# TP1_NodoWiFi_Pwr_Rev0.net
KiCad netlist of a schematic drawn in Altium Designer
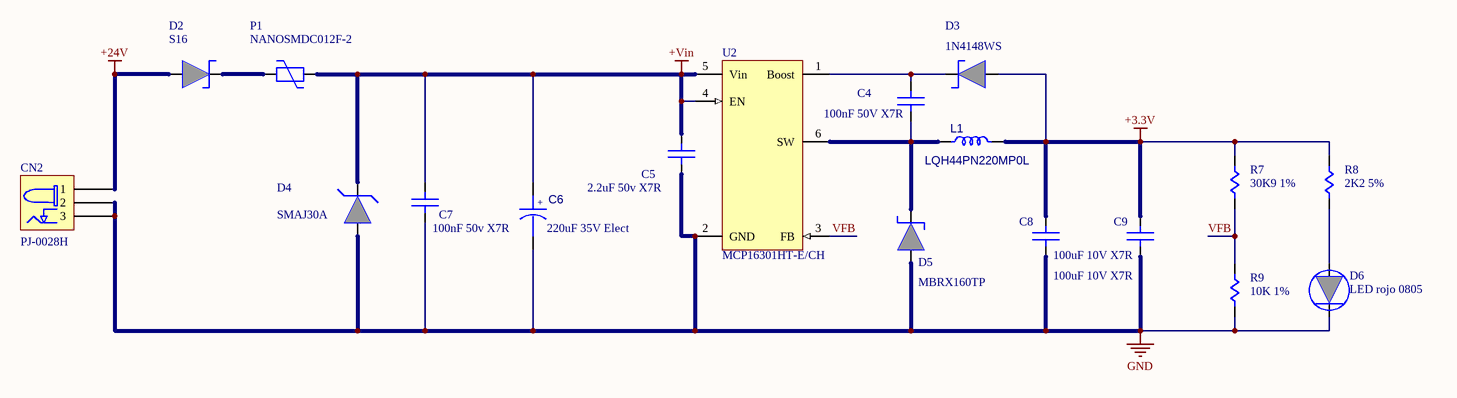
[diagram p0: TP1_NodoWiFi_Pwr_Rev0.SchDoc]

(export (version "E")
  (design (tool "Eeschema 10.0.6"))
  (components
    (comp (ref "C4")
      (value "100nF 50V X7R")
      (footprint "IDCI_WifiNode:C_0805")
      (description "capacitor no polarizado")
      (libsource (lib "WifiNode") (part "Capacitor_NoP"))
    )
    (comp (ref "C5")
      (value "2.2uF 50v X7R")
      (footprint "IDCI_WifiNode:C_0805")
      (description "capacitor no polarizado")
      (libsource (lib "WifiNode") (part "Capacitor_NoP"))
    )
    (comp (ref "C6")
      (value "220uF 35V Elect")
      (footprint "IDCI_WifiNode:C_RAD_0.135_H_8X12_S")
      (description "Polarized Capacitor")
      (libsource (lib "WifiNode") (part "CAP_P"))
    )
    (comp (ref "C7")
      (value "100nF 50v X7R")
      (footprint "IDCI_WifiNode:C_0805")
      (description "capacitor no polarizado")
      (libsource (lib "WifiNode") (part "Capacitor_NoP"))
    )
    (comp (ref "C8")
      (value "100uF 10V X7R")
      (footprint "IDCI_WifiNode:C_0805")
      (description "capacitor no polarizado")
      (libsource (lib "WifiNode") (part "Capacitor_NoP"))
    )
    (comp (ref "C9")
      (value "100uF 10V X7R")
      (footprint "IDCI_WifiNode:C_0805")
      (description "capacitor no polarizado")
      (libsource (lib "WifiNode") (part "Capacitor_NoP"))
    )
    (comp (ref "CN2")
      (value "PJ-0028H")
      (footprint "IDCI_WifiNode:PJ002B")
      (description "Conector PJ")
      (libsource (lib "WifiNode") (part "PJ-0028H"))
    )
    (comp (ref "D2")
      (value "S16")
      (footprint "IDCI_WifiNode:D_0805")
      (description "Schottky")
      (libsource (lib "WifiNode") (part "Diodo Schottky"))
    )
    (comp (ref "D3")
      (value "1N4148WS")
      (footprint "IDCI_WifiNode:D_0805")
      (description "Schottky")
      (libsource (lib "WifiNode") (part "Diodo Schottky"))
    )
    (comp (ref "D4")
      (value "SMAJ30A")
      (footprint "IDCI_WifiNode:D_SMA")
      (description "Zener")
      (libsource (lib "WifiNode") (part "Diodo Zener"))
    )
    (comp (ref "D5")
      (value "MBRX160TP")
      (footprint "IDCI_WifiNode:SOD_123")
      (description "Schottky")
      (libsource (lib "WifiNode") (part "Diodo Schottky"))
    )
    (comp (ref "D6")
      (value "LED rojo 0805")
      (footprint "IDCI_WifiNode:D_0805")
      (description "LED")
      (libsource (lib "WifiNode") (part "Diodo LED"))
    )
    (comp (ref "L1")
      (value "LQH44PN220MP0L")
      (footprint "IDCI_WifiNode:LQH44")
      (description "Inductor")
      (libsource (lib "WifiNode") (part "IND"))
    )
    (comp (ref "P1")
      (value "NANOSMDC012F-2")
      (footprint "IDCI_WifiNode:C_1206")
      (description "Poly Switch")
      (libsource (lib "WifiNode") (part "Poly Switch"))
    )
    (comp (ref "R7")
      (value "30K9 1%")
      (footprint "IDCI_WifiNode:R_0805")
      (description "Resistor")
      (libsource (lib "WifiNode") (part "Resistencia"))
    )
    (comp (ref "R8")
      (value "2K2 5%")
      (footprint "IDCI_WifiNode:R_0805")
      (description "Resistor")
      (libsource (lib "WifiNode") (part "Resistencia"))
    )
    (comp (ref "R9")
      (value "10K 1%")
      (footprint "IDCI_WifiNode:R_0805")
      (description "Resistor")
      (libsource (lib "WifiNode") (part "Resistencia"))
    )
    (comp (ref "U2")
      (value "MCP16301HT-E/CH")
      (footprint "IDCI_WifiNode:SOT23-6")
      (description "IC_DC/DC Buck controler")
      (libsource (lib "WifiNode") (part "MCP16301"))
    )
  )
  (nets
    (net (code "1") (name "+3.3V") (class "Default")
      (node (ref "C8") (pin "2") (pinfunction "Cap_2") (pintype "passive"))
      (node (ref "C9") (pin "2") (pinfunction "Cap_2") (pintype "passive"))
      (node (ref "D3") (pin "1") (pinfunction "Cap_1") (pintype "passive"))
      (node (ref "L1") (pin "2") (pinfunction "2_2") (pintype "passive"))
      (node (ref "R7") (pin "2") (pinfunction "Cap_2") (pintype "passive"))
      (node (ref "R8") (pin "2") (pinfunction "Cap_2") (pintype "passive"))
    )
    (net (code "2") (name "+24V") (class "Default")
      (node (ref "CN2") (pin "1") (pinfunction "1_1") (pintype "power_in"))
      (node (ref "D2") (pin "1") (pinfunction "Cap_1") (pintype "passive"))
    )
    (net (code "3") (name "+Vin") (class "Default")
      (node (ref "C5") (pin "2") (pinfunction "Cap_2") (pintype "passive"))
      (node (ref "C6") (pin "1") (pinfunction "1_1") (pintype "passive"))
      (node (ref "C7") (pin "2") (pinfunction "Cap_2") (pintype "passive"))
      (node (ref "D4") (pin "2") (pinfunction "Cap_2") (pintype "passive"))
      (node (ref "P1") (pin "1") (pinfunction "Cap_1") (pintype "passive"))
      (node (ref "U2") (pin "4") (pinfunction "EN_4") (pintype "input"))
      (node (ref "U2") (pin "5") (pinfunction "Vin_5") (pintype "power_in"))
    )
    (net (code "4") (name "/VFB") (class "Default")
      (node (ref "R7") (pin "1") (pinfunction "Cap_1") (pintype "passive"))
      (node (ref "R9") (pin "2") (pinfunction "Cap_2") (pintype "passive"))
      (node (ref "U2") (pin "3") (pinfunction "FB_3") (pintype "input"))
    )
    (net (code "5") (name "GND") (class "Default")
      (node (ref "C5") (pin "1") (pinfunction "Cap_1") (pintype "passive"))
      (node (ref "C6") (pin "2") (pinfunction "2_2") (pintype "passive"))
      (node (ref "C7") (pin "1") (pinfunction "Cap_1") (pintype "passive"))
      (node (ref "C8") (pin "1") (pinfunction "Cap_1") (pintype "passive"))
      (node (ref "C9") (pin "1") (pinfunction "Cap_1") (pintype "passive"))
      (node (ref "CN2") (pin "2") (pinfunction "2_2") (pintype "power_in"))
      (node (ref "CN2") (pin "3") (pinfunction "3_3") (pintype "power_in"))
      (node (ref "D4") (pin "1") (pinfunction "Cap_1") (pintype "passive"))
      (node (ref "D5") (pin "1") (pinfunction "Cap_1") (pintype "passive"))
      (node (ref "D6") (pin "2") (pinfunction "Cap_2") (pintype "passive"))
      (node (ref "R9") (pin "1") (pinfunction "Cap_1") (pintype "passive"))
      (node (ref "U2") (pin "2") (pinfunction "GND_2") (pintype "power_in"))
    )
    (net (code "6") (name "Net-(D2-Cap-Pad2)") (class "Default")
      (node (ref "D2") (pin "2") (pinfunction "Cap_2") (pintype "passive"))
      (node (ref "P1") (pin "2") (pinfunction "Cap_2") (pintype "passive"))
    )
    (net (code "7") (name "Net-(D6-Cap-Pad1)") (class "Default")
      (node (ref "D6") (pin "1") (pinfunction "Cap_1") (pintype "passive"))
      (node (ref "R8") (pin "1") (pinfunction "Cap_1") (pintype "passive"))
    )
    (net (code "8") (name "Net-(U2-Boost)") (class "Default")
      (node (ref "C4") (pin "2") (pinfunction "Cap_2") (pintype "passive"))
      (node (ref "D3") (pin "2") (pinfunction "Cap_2") (pintype "passive"))
      (node (ref "U2") (pin "1") (pinfunction "Boost_1") (pintype "passive"))
    )
    (net (code "9") (name "Net-(U2-SW)") (class "Default")
      (node (ref "C4") (pin "1") (pinfunction "Cap_1") (pintype "passive"))
      (node (ref "D5") (pin "2") (pinfunction "Cap_2") (pintype "passive"))
      (node (ref "L1") (pin "1") (pinfunction "1_1") (pintype "passive"))
      (node (ref "U2") (pin "6") (pinfunction "SW_6") (pintype "power_in"))
    )
  )
)
